# CAS_5.net
KiCad netlist of a schematic drawn in Altium Designer
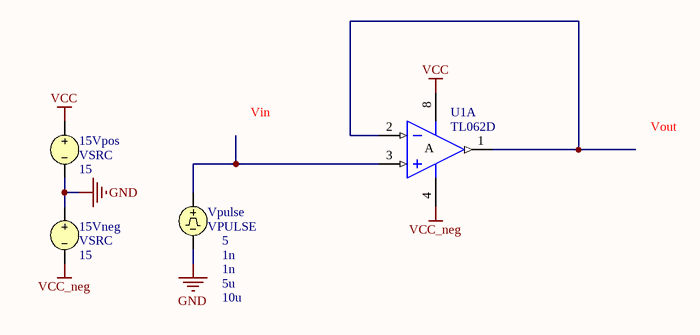
[diagram p0: CAS_5.SchDoc]

(export (version "E")
  (design (tool "Eeschema 10.0.6"))
  (components
    (comp (ref "15Vneg")
      (value "VSRC")
      (description "Voltage Source")
      (fields (field (name "ALTIUM_VALUE") "15") (field (name "PUBLISHER") "Altium Limited"))
      (libsource (lib "Simulation Generic Components") (part "VSRC"))
    )
    (comp (ref "15Vpos")
      (value "VSRC")
      (description "Voltage Source")
      (fields (field (name "ALTIUM_VALUE") "15") (field (name "PUBLISHER") "Altium Limited"))
      (libsource (lib "Simulation Generic Components") (part "VSRC"))
    )
    (comp (ref "U1")
      (value "TL062D")
      (footprint "D008_L")
      (description "Low-Power JFET-Input Operational Amplifier")
      (fields (field (name "PUBLISHER") "Altium Limited"))
      (libsource (lib "TI Operational Amplifier") (part "TL062D"))
    )
    (comp (ref "Vpulse")
      (value "VPULSE")
      (description "Pulse Voltage Source")
      (fields
        (field (name "PULSED VALUE") "5")
        (field (name "RISE TIME") "1n")
        (field (name "FALL TIME") "1n")
        (field (name "PULSE WIDTH") "5u")
        (field (name "PERIOD") "10u")
        (field (name "PUBLISHER") "Altium Limited")
      )
      (libsource (lib "Simulation Sources") (part "VPULSE"))
    )
  )
  (nets
    (net (code "1") (name "GND") (class "Default")
      (node (ref "15Vneg") (pin "1") (pinfunction "1_1") (pintype "passive"))
      (node (ref "15Vpos") (pin "2") (pinfunction "2_2") (pintype "passive"))
      (node (ref "Vpulse") (pin "2") (pinfunction "2_2") (pintype "passive"))
    )
    (net (code "2") (name "Net-(U1A-IN+)") (class "Default")
      (node (ref "U1") (pin "3") (pinfunction "IN+_3") (pintype "input"))
      (node (ref "Vpulse") (pin "1") (pinfunction "1_1") (pintype "passive"))
    )
    (net (code "3") (name "Net-(U1A-IN-)") (class "Default")
      (node (ref "U1") (pin "1") (pinfunction "OUT_1") (pintype "output"))
      (node (ref "U1") (pin "2") (pinfunction "IN-_2") (pintype "input"))
    )
    (net (code "4") (name "VCC") (class "Default")
      (node (ref "15Vpos") (pin "1") (pinfunction "1_1") (pintype "passive"))
      (node (ref "U1") (pin "8") (pinfunction "V+_8") (pintype "power_in"))
    )
    (net (code "5") (name "VCC_neg") (class "Default")
      (node (ref "15Vneg") (pin "2") (pinfunction "2_2") (pintype "passive"))
      (node (ref "U1") (pin "4") (pinfunction "V-_4") (pintype "power_in"))
    )
  )
)
